# Relay_Control_Outputs.net
KiCad netlist of a schematic drawn in Altium Designer
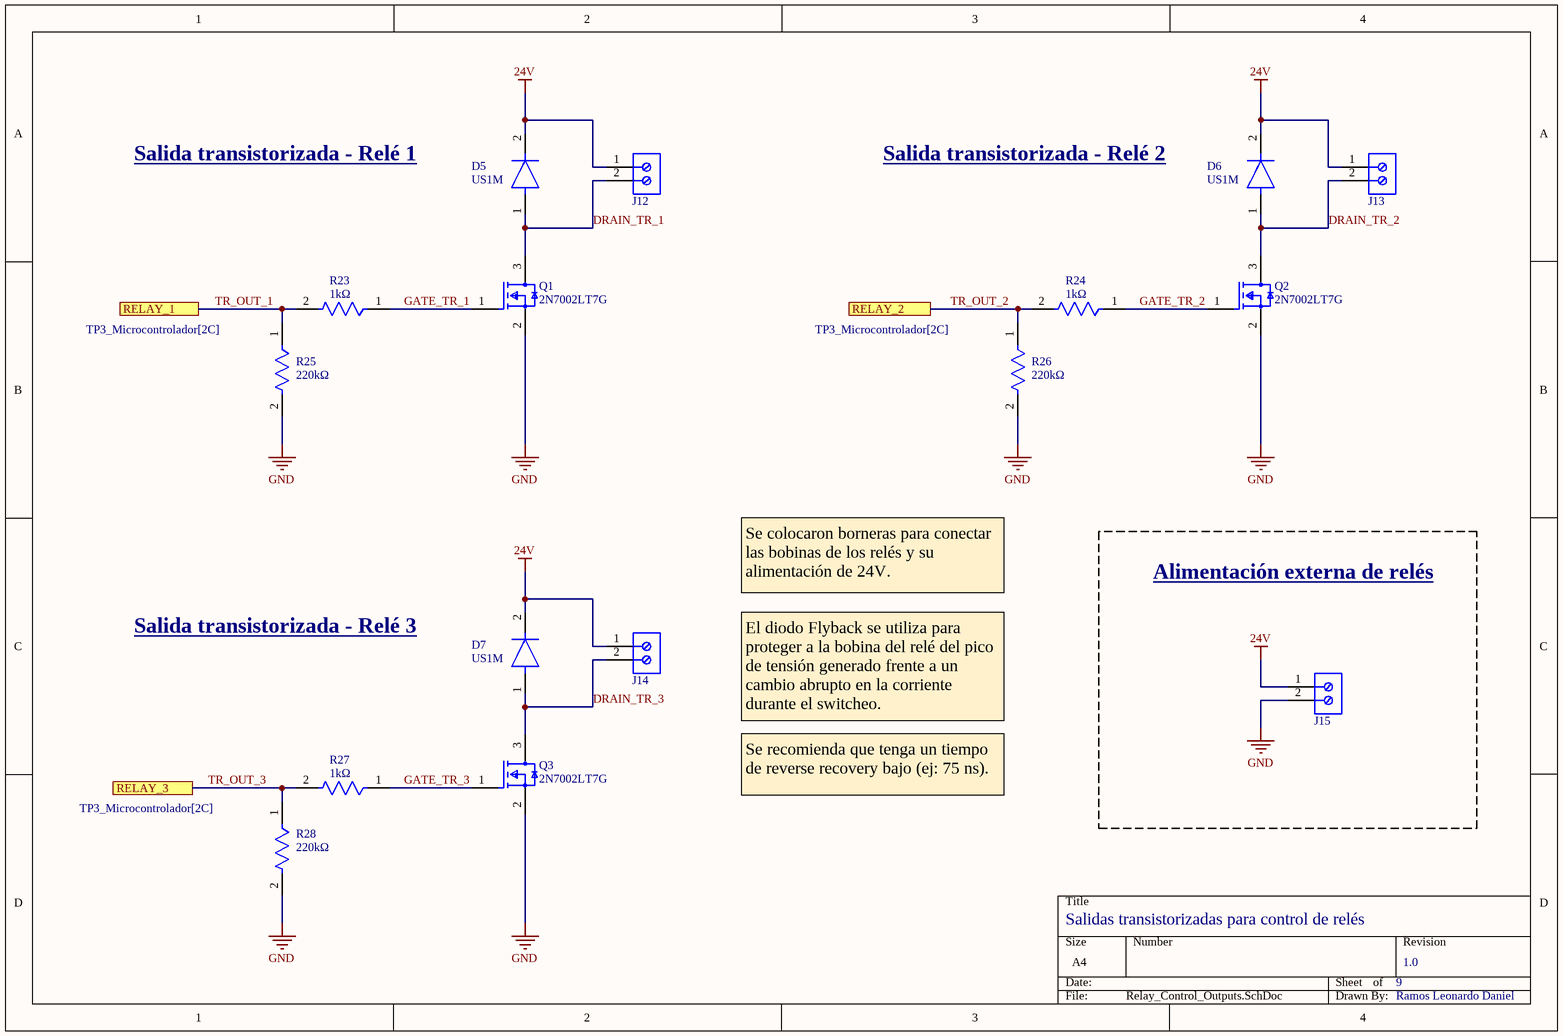
[diagram p0: Relay_Control_Outputs.SchDoc]

(export (version "E")
  (design (tool "Eeschema 10.0.6"))
  (components
    (comp (ref "D5")
      (value "US1M")
      (footprint "SMA_DO-214AC")
      (description "Simbolo genérico de diodo.")
      (libsource (lib "Componentes_custom") (part "Diode"))
    )
    (comp (ref "D6")
      (value "US1M")
      (footprint "SMA_DO-214AC")
      (description "Simbolo genérico de diodo.")
      (libsource (lib "Componentes_custom") (part "Diode"))
    )
    (comp (ref "D7")
      (value "US1M")
      (footprint "SMA_DO-214AC")
      (description "Simbolo genérico de diodo.")
      (libsource (lib "Componentes_custom") (part "Diode"))
    )
    (comp (ref "J12")
      (value "691137710002")
      (footprint "691137710002")
      (libsource (lib "Altium Content Vault") (part "TBL - 1R - 02P - Screw"))
    )
    (comp (ref "J13")
      (value "691137710002")
      (footprint "691137710002")
      (libsource (lib "Altium Content Vault") (part "TBL - 1R - 02P - Screw"))
    )
    (comp (ref "J14")
      (value "691137710002")
      (footprint "691137710002")
      (libsource (lib "Altium Content Vault") (part "TBL - 1R - 02P - Screw"))
    )
    (comp (ref "J15")
      (value "691137710002")
      (footprint "691137710002")
      (libsource (lib "Altium Content Vault") (part "TBL - 1R - 02P - Screw"))
    )
    (comp (ref "Q1")
      (value "2N7002LT7G")
      (footprint "FP-318-MFG")
      (description "2N7002LT7G SOT23, N-Channel MOSFET - 60V 115MA 7.5Ohm SOT23, N-Ch Mosfet - 60V 115MA 7.5O")
      (libsource (lib "Altium Content Vault") (part "b87e6fbdfc493b6de00281388569415"))
    )
    (comp (ref "Q2")
      (value "2N7002LT7G")
      (footprint "FP-318-MFG")
      (description "2N7002LT7G SOT23, N-Channel MOSFET - 60V 115MA 7.5Ohm SOT23, N-Ch Mosfet - 60V 115MA 7.5O")
      (libsource (lib "Altium Content Vault") (part "b87e6fbdfc493b6de00281388569415"))
    )
    (comp (ref "Q3")
      (value "2N7002LT7G")
      (footprint "FP-318-MFG")
      (description "2N7002LT7G SOT23, N-Channel MOSFET - 60V 115MA 7.5Ohm SOT23, N-Ch Mosfet - 60V 115MA 7.5O")
      (libsource (lib "Altium Content Vault") (part "b87e6fbdfc493b6de00281388569415"))
    )
    (comp (ref "R23")
      (value "CRCW08054K70JNEA")
      (footprint "FP-CRCW0805-e3-IPC_B")
      (description "RES Thick Film, 1kΩ, 5%, 0.125W, 200ppm/°C, 0805")
      (fields (field (name "TOLERANCE") "5%") (field (name "RESISTANCE") "1kΩ"))
      (libsource (lib "Altium Content Vault") (part "1029c3af85768c4190bb7ad29bc67b5"))
    )
    (comp (ref "R24")
      (value "CRCW08054K70JNEA")
      (footprint "FP-CRCW0805-e3-IPC_B")
      (description "RES Thick Film, 1kΩ, 5%, 0.125W, 200ppm/°C, 0805")
      (fields (field (name "TOLERANCE") "5%") (field (name "RESISTANCE") "1kΩ"))
      (libsource (lib "Altium Content Vault") (part "1029c3af85768c4190bb7ad29bc67b5"))
    )
    (comp (ref "R25")
      (value "CRCW08054K70JNEA")
      (footprint "FP-CRCW0805-e3-IPC_B")
      (description "RES Thick Film, 10kΩ, 5%, 0.125W, 200ppm/°C, 0805")
      (fields (field (name "TOLERANCE") "5%") (field (name "RESISTANCE") "220kΩ"))
      (libsource (lib "Altium Content Vault") (part "1029c3af85768c4190bb7ad29bc67b5"))
    )
    (comp (ref "R26")
      (value "CRCW08054K70JNEA")
      (footprint "FP-CRCW0805-e3-IPC_B")
      (description "RES Thick Film, 10kΩ, 5%, 0.125W, 200ppm/°C, 0805")
      (fields (field (name "TOLERANCE") "5%") (field (name "RESISTANCE") "220kΩ"))
      (libsource (lib "Altium Content Vault") (part "1029c3af85768c4190bb7ad29bc67b5"))
    )
    (comp (ref "R27")
      (value "CRCW08054K70JNEA")
      (footprint "FP-CRCW0805-e3-IPC_B")
      (description "RES Thick Film, 1kΩ, 5%, 0.125W, 200ppm/°C, 0805")
      (fields (field (name "TOLERANCE") "5%") (field (name "RESISTANCE") "1kΩ"))
      (libsource (lib "Altium Content Vault") (part "1029c3af85768c4190bb7ad29bc67b5"))
    )
    (comp (ref "R28")
      (value "CRCW08054K70JNEA")
      (footprint "FP-CRCW0805-e3-IPC_B")
      (description "RES Thick Film, 10kΩ, 5%, 0.125W, 200ppm/°C, 0805")
      (fields (field (name "TOLERANCE") "5%") (field (name "RESISTANCE") "220kΩ"))
      (libsource (lib "Altium Content Vault") (part "1029c3af85768c4190bb7ad29bc67b5"))
    )
  )
  (nets
    (net (code "1") (name "/DRAIN_TR_1") (class "Default")
      (node (ref "D5") (pin "1") (pinfunction "A_1") (pintype "passive"))
      (node (ref "J12") (pin "2") (pinfunction "2_2") (pintype "passive"))
      (node (ref "Q1") (pin "3") (pinfunction "Drain_3") (pintype "passive"))
    )
    (net (code "2") (name "/DRAIN_TR_2") (class "Default")
      (node (ref "D6") (pin "1") (pinfunction "A_1") (pintype "passive"))
      (node (ref "J13") (pin "2") (pinfunction "2_2") (pintype "passive"))
      (node (ref "Q2") (pin "3") (pinfunction "Drain_3") (pintype "passive"))
    )
    (net (code "3") (name "/DRAIN_TR_3") (class "Default")
      (node (ref "D7") (pin "1") (pinfunction "A_1") (pintype "passive"))
      (node (ref "J14") (pin "2") (pinfunction "2_2") (pintype "passive"))
      (node (ref "Q3") (pin "3") (pinfunction "Drain_3") (pintype "passive"))
    )
    (net (code "4") (name "/GATE_TR_1") (class "Default")
      (node (ref "Q1") (pin "1") (pinfunction "Gate_1") (pintype "passive"))
      (node (ref "R23") (pin "1") (pinfunction "1_1") (pintype "passive"))
    )
    (net (code "5") (name "/GATE_TR_2") (class "Default")
      (node (ref "Q2") (pin "1") (pinfunction "Gate_1") (pintype "passive"))
      (node (ref "R24") (pin "1") (pinfunction "1_1") (pintype "passive"))
    )
    (net (code "6") (name "/GATE_TR_3") (class "Default")
      (node (ref "Q3") (pin "1") (pinfunction "Gate_1") (pintype "passive"))
      (node (ref "R27") (pin "1") (pinfunction "1_1") (pintype "passive"))
    )
    (net (code "7") (name "/TR_OUT_1") (class "Default")
      (node (ref "R23") (pin "2") (pinfunction "2_2") (pintype "passive"))
      (node (ref "R25") (pin "1") (pinfunction "1_1") (pintype "passive"))
    )
    (net (code "8") (name "/TR_OUT_2") (class "Default")
      (node (ref "R24") (pin "2") (pinfunction "2_2") (pintype "passive"))
      (node (ref "R26") (pin "1") (pinfunction "1_1") (pintype "passive"))
    )
    (net (code "9") (name "/TR_OUT_3") (class "Default")
      (node (ref "R27") (pin "2") (pinfunction "2_2") (pintype "passive"))
      (node (ref "R28") (pin "1") (pinfunction "1_1") (pintype "passive"))
    )
    (net (code "10") (name "24V") (class "Default")
      (node (ref "D5") (pin "2") (pinfunction "K_2") (pintype "passive"))
      (node (ref "D6") (pin "2") (pinfunction "K_2") (pintype "passive"))
      (node (ref "D7") (pin "2") (pinfunction "K_2") (pintype "passive"))
      (node (ref "J12") (pin "1") (pinfunction "1_1") (pintype "passive"))
      (node (ref "J13") (pin "1") (pinfunction "1_1") (pintype "passive"))
      (node (ref "J14") (pin "1") (pinfunction "1_1") (pintype "passive"))
      (node (ref "J15") (pin "1") (pinfunction "1_1") (pintype "passive"))
    )
    (net (code "11") (name "GND") (class "Default")
      (node (ref "J15") (pin "2") (pinfunction "2_2") (pintype "passive"))
      (node (ref "Q1") (pin "2") (pinfunction "Source_2") (pintype "passive"))
      (node (ref "Q2") (pin "2") (pinfunction "Source_2") (pintype "passive"))
      (node (ref "Q3") (pin "2") (pinfunction "Source_2") (pintype "passive"))
      (node (ref "R25") (pin "2") (pinfunction "2_2") (pintype "passive"))
      (node (ref "R26") (pin "2") (pinfunction "2_2") (pintype "passive"))
      (node (ref "R28") (pin "2") (pinfunction "2_2") (pintype "passive"))
    )
  )
)
